# EBS_2020.net
KiCad netlist of a schematic drawn in Altium Designer
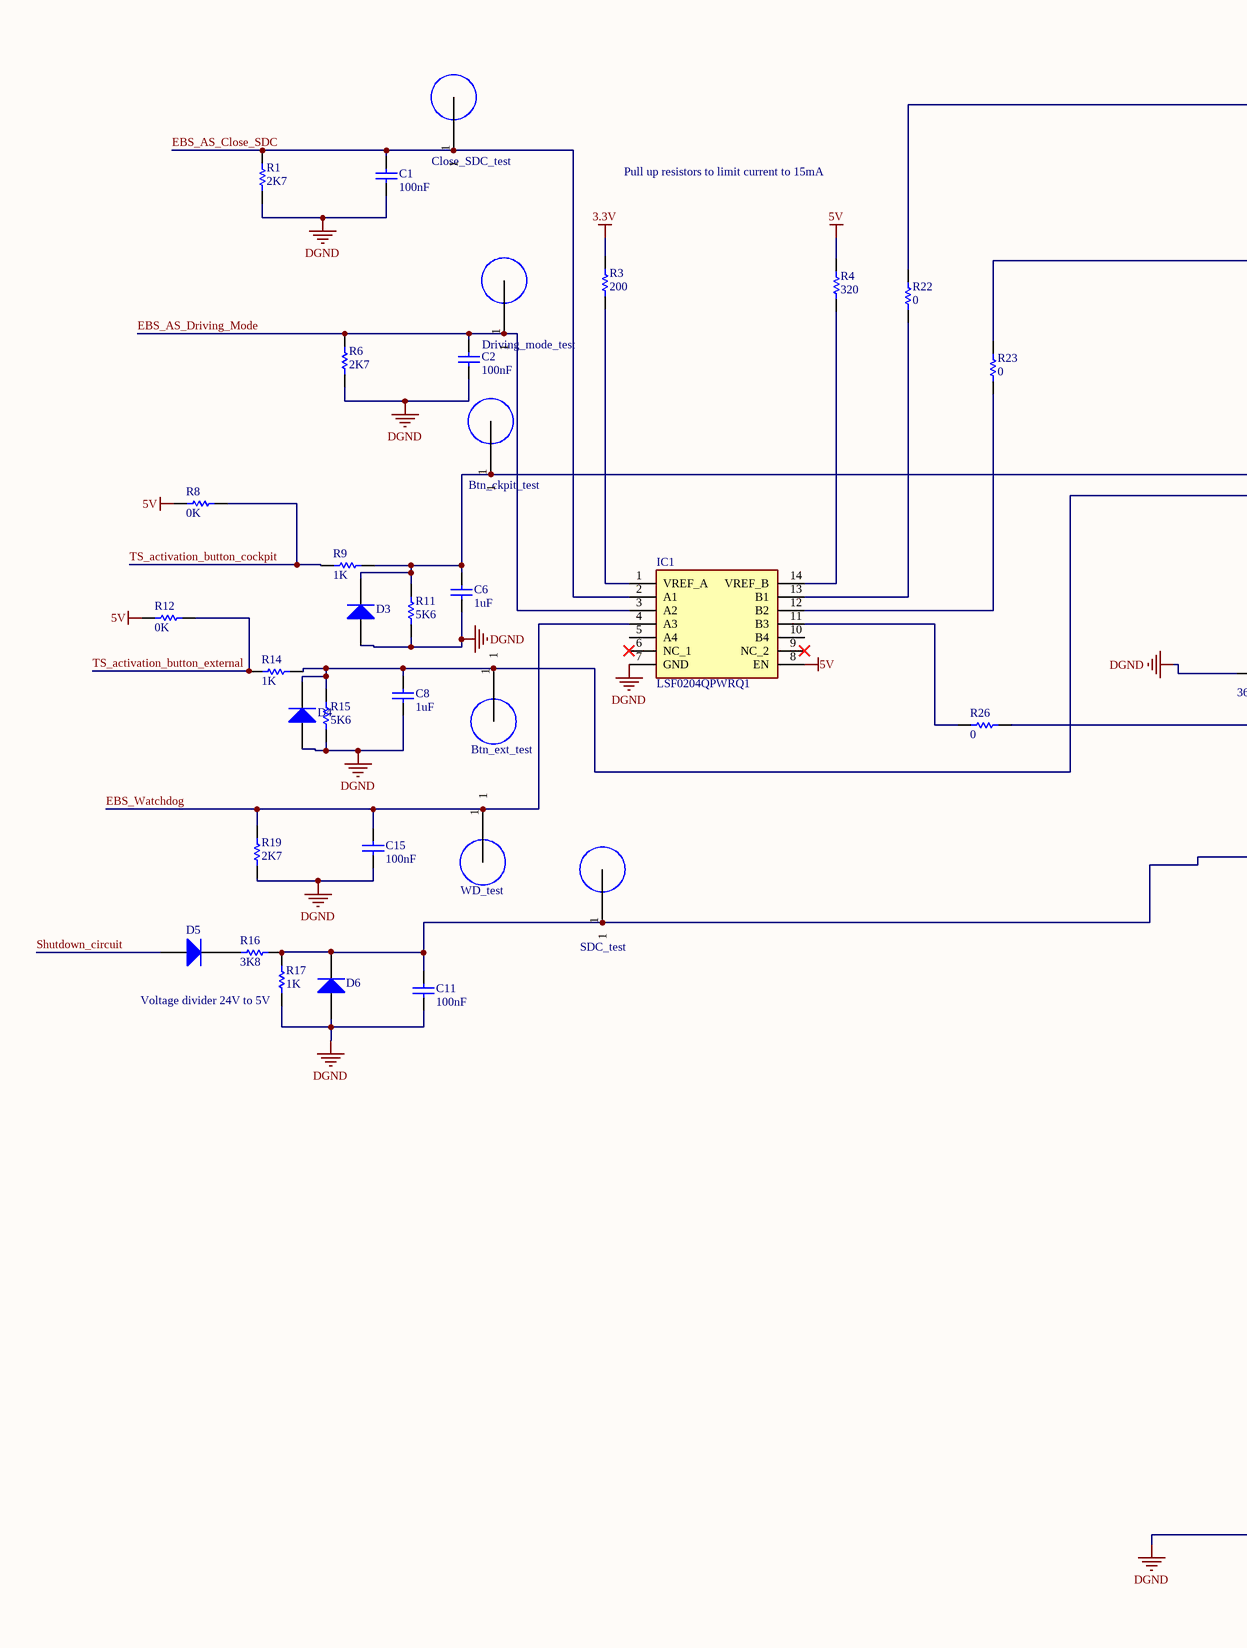
[diagram p0: EBS_2020.SchDoc, left]
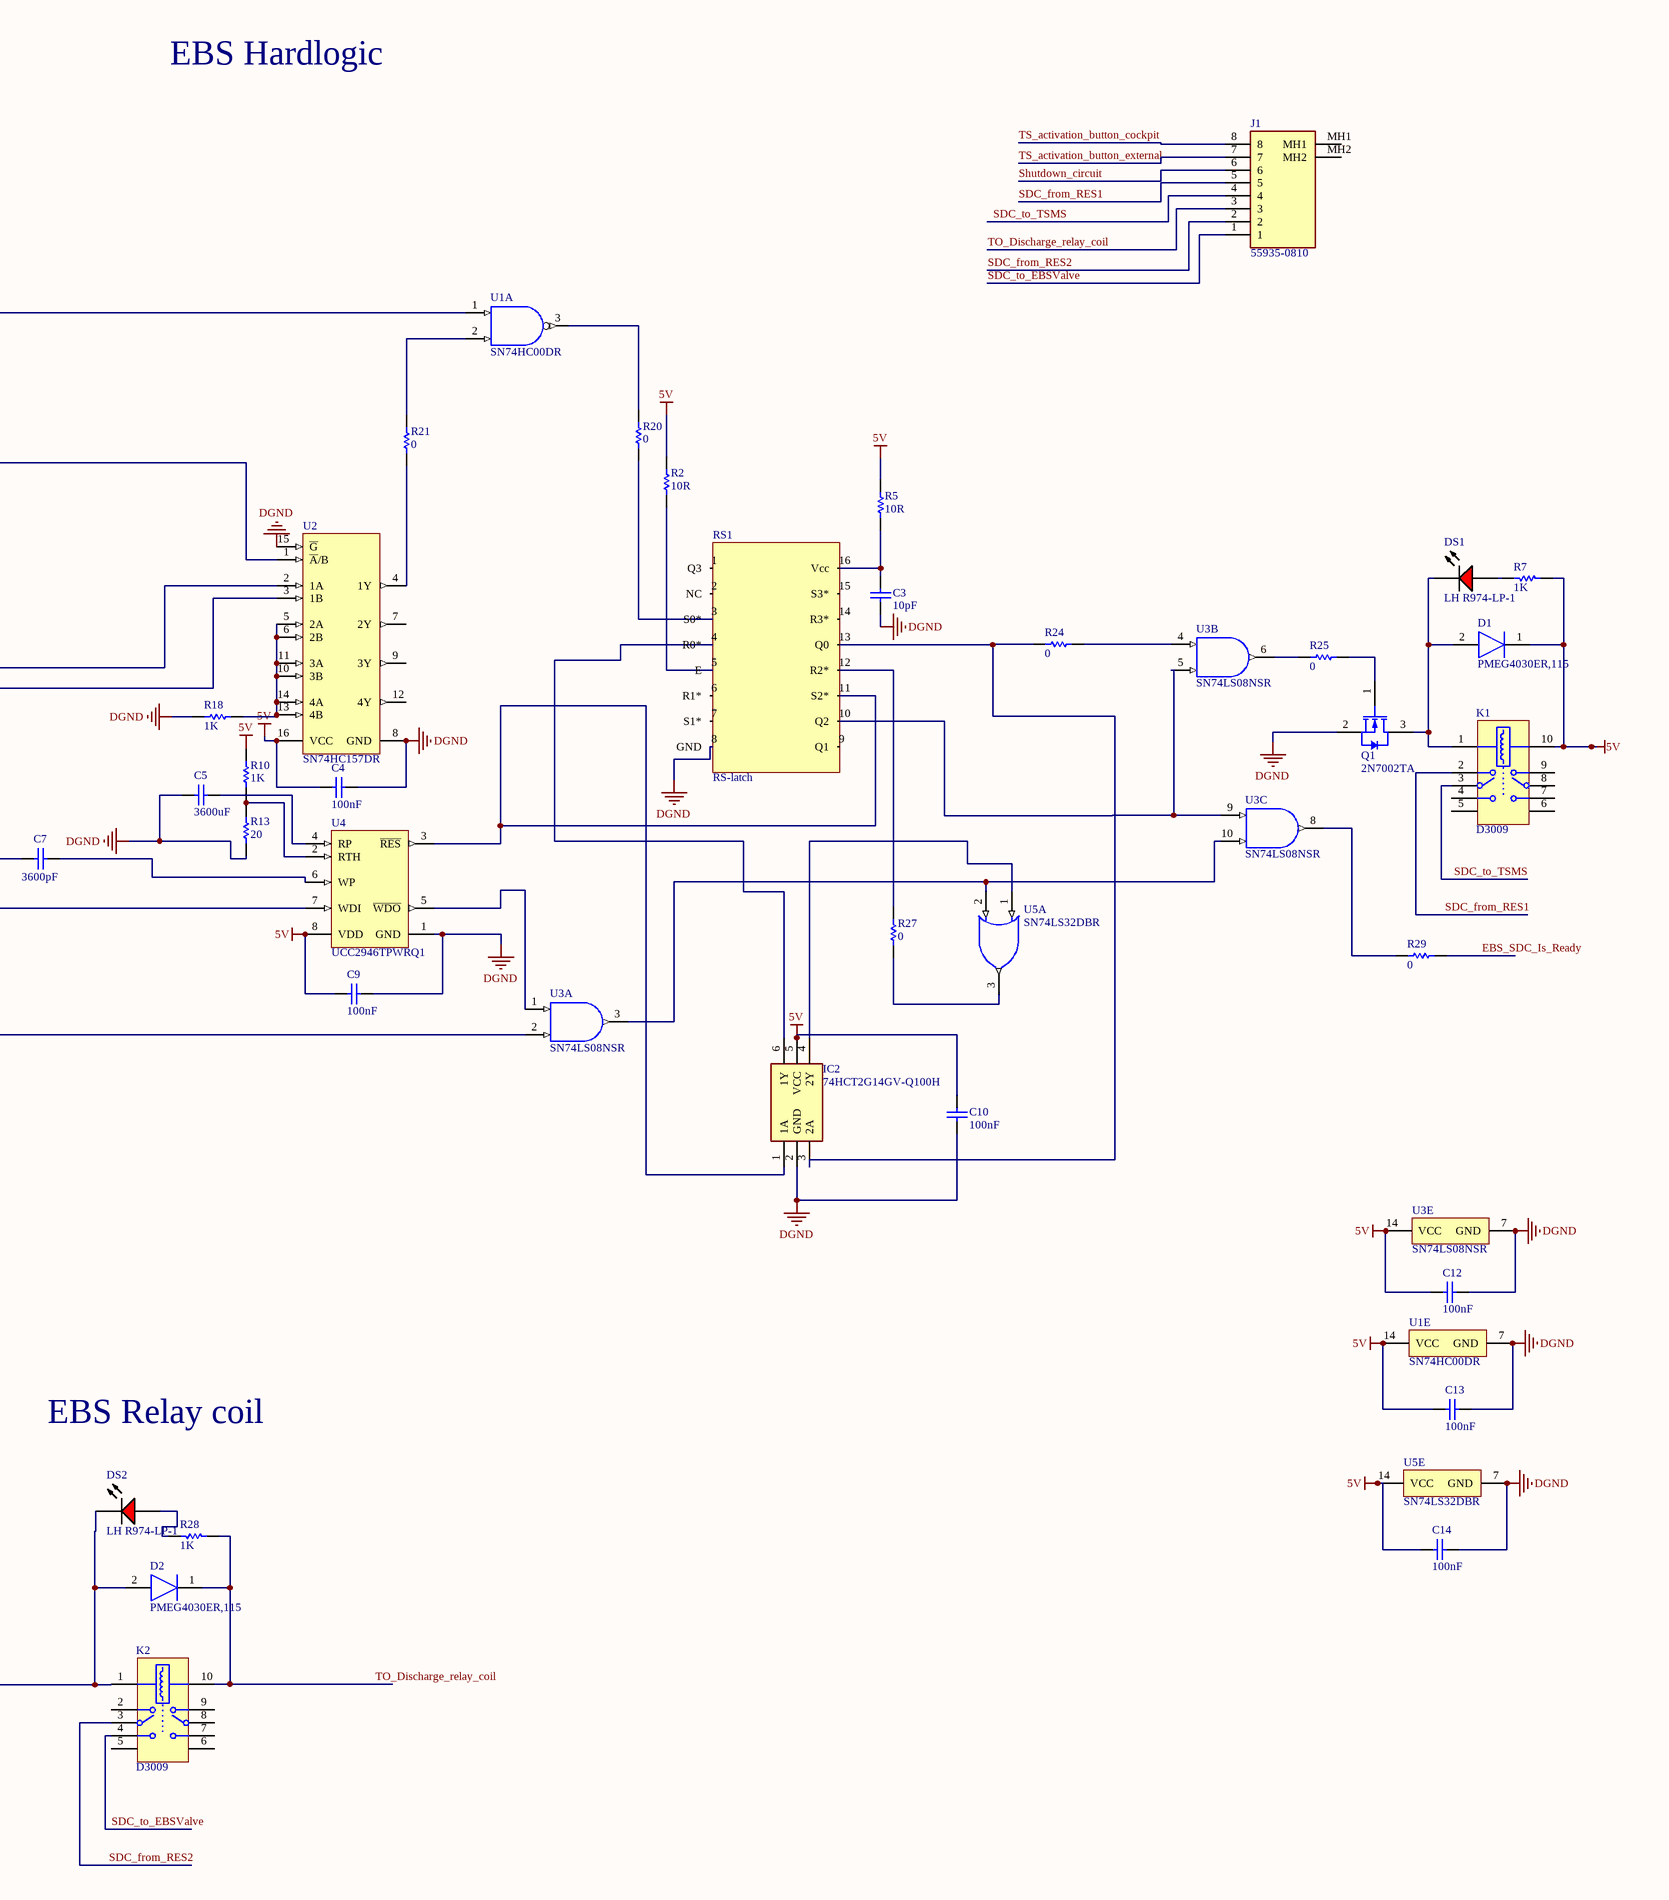
[diagram p1: EBS_2020.SchDoc, right]

(export (version "E")
  (design (tool "Eeschema 10.0.6"))
  (components
    (comp (ref "Btn_ckpit_test")
      (value "MeasuringPoint")
      (footprint "MeasuringPoint")
      (description "1,2mm hole for measuring purpose. Designator should be signal name.")
      (libsource (lib "MeasuringPoint") (part "MeasuringPoint"))
    )
    (comp (ref "Btn_ext_test")
      (value "MeasuringPoint")
      (footprint "MeasuringPoint")
      (description "1,2mm hole for measuring purpose. Designator should be signal name.")
      (libsource (lib "MeasuringPoint") (part "MeasuringPoint"))
    )
    (comp (ref "C1")
      (value "100nF")
      (footprint "dV_C0805")
      (description "CAP 100nF 10V ±20% 0805 (2012 Metric) Thickness 0.75mm SMD")
      (fields (field (name "TOLERANCE") "Â±20%"))
      (libsource (lib "Miscellaneous Devices") (part "CAP"))
    )
    (comp (ref "C2")
      (value "100nF")
      (footprint "dV_C0805")
      (description "CAP 100nF 10V ±20% 0805 (2012 Metric) Thickness 0.75mm SMD")
      (fields (field (name "TOLERANCE") "Â±20%"))
      (libsource (lib "Miscellaneous Devices") (part "CAP"))
    )
    (comp (ref "C3")
      (value "10pF")
      (footprint "CAPC0805(2012)100_N")
      (description "CAP 10pF 16V ±0.5pF 0805 (2012 Metric) Thickness 1mm SMD")
      (fields (field (name "TOLERANCE") "Â±0.5pF"))
      (libsource (lib "Altium Content Vault") (part "CAP"))
    )
    (comp (ref "C4")
      (value "100nF")
      (footprint "dV_C0805")
      (description "CAP 100nF 10V ±20% 0805 (2012 Metric) Thickness 0.75mm SMD")
      (fields (field (name "TOLERANCE") "Â±20%"))
      (libsource (lib "Miscellaneous Devices") (part "CAP"))
    )
    (comp (ref "C5")
      (value "3600uF")
      (footprint "dV_C0805")
      (description "CAP 100nF 10V ±20% 0805 (2012 Metric) Thickness 0.75mm SMD")
      (fields (field (name "TOLERANCE") "Â±20%"))
      (libsource (lib "Miscellaneous Devices") (part "CAP"))
    )
    (comp (ref "C6")
      (value "1uF")
      (footprint "dV_C0805")
      (description "CAP 100nF 10V ±20% 0805 (2012 Metric) Thickness 0.75mm SMD")
      (fields (field (name "TOLERANCE") "Â±20%"))
      (libsource (lib "Miscellaneous Devices") (part "CAP"))
    )
    (comp (ref "C7")
      (value "3600pF")
      (footprint "dV_C0805")
      (fields
        (field (name "MANUFACTURER") "KEMET")
        (field (name "MANUFACTURER PART NUMBER") "C1206C362J5GACTU")
        (field (name "VOLTAGE") "50VDC")
      )
      (libsource (lib "altium-import") (part "root_2_Cap_"))
    )
    (comp (ref "C8")
      (value "1uF")
      (footprint "dV_C0805")
      (description "CAP 100nF 10V ±20% 0805 (2012 Metric) Thickness 0.75mm SMD")
      (fields (field (name "TOLERANCE") "Â±20%"))
      (libsource (lib "Miscellaneous Devices") (part "CAP"))
    )
    (comp (ref "C9")
      (value "100nF")
      (footprint "dV_C0805")
      (description "CAP 100nF 10V ±20% 0805 (2012 Metric) Thickness 0.75mm SMD")
      (fields (field (name "TOLERANCE") "Â±20%"))
      (libsource (lib "Miscellaneous Devices") (part "CAP"))
    )
    (comp (ref "C10")
      (value "100nF")
      (footprint "dV_C0805")
      (description "CAP 100nF 10V ±20% 0805 (2012 Metric) Thickness 0.75mm SMD")
      (fields (field (name "TOLERANCE") "Â±20%"))
      (libsource (lib "Miscellaneous Devices") (part "CAP"))
    )
    (comp (ref "C11")
      (value "100nF")
      (footprint "dV_C0805")
      (description "CAP 100nF 10V ±20% 0805 (2012 Metric) Thickness 0.75mm SMD")
      (fields (field (name "TOLERANCE") "Â±20%"))
      (libsource (lib "Miscellaneous Devices") (part "CAP"))
    )
    (comp (ref "C12")
      (value "100nF")
      (footprint "dV_C0805")
      (description "CAP 100nF 10V ±20% 0805 (2012 Metric) Thickness 0.75mm SMD")
      (fields (field (name "TOLERANCE") "Â±20%"))
      (libsource (lib "Miscellaneous Devices") (part "CAP"))
    )
    (comp (ref "C13")
      (value "100nF")
      (footprint "dV_C0805")
      (description "CAP 100nF 10V ±20% 0805 (2012 Metric) Thickness 0.75mm SMD")
      (fields (field (name "TOLERANCE") "Â±20%"))
      (libsource (lib "Miscellaneous Devices") (part "CAP"))
    )
    (comp (ref "C14")
      (value "100nF")
      (footprint "dV_C0805")
      (description "CAP 100nF 10V ±20% 0805 (2012 Metric) Thickness 0.75mm SMD")
      (fields (field (name "TOLERANCE") "Â±20%"))
      (libsource (lib "Miscellaneous Devices") (part "CAP"))
    )
    (comp (ref "C15")
      (value "100nF")
      (footprint "dV_C0805")
      (description "CAP 100nF 10V ±20% 0805 (2012 Metric) Thickness 0.75mm SMD")
      (fields (field (name "TOLERANCE") "Â±20%"))
      (libsource (lib "Miscellaneous Devices") (part "CAP"))
    )
    (comp (ref "Close_SDC_test")
      (value "MeasuringPoint")
      (footprint "MeasuringPoint")
      (description "1,2mm hole for measuring purpose. Designator should be signal name.")
      (libsource (lib "MeasuringPoint") (part "MeasuringPoint"))
    )
    (comp (ref "D1")
      (value "PMEG4030ER,115")
      (footprint "SamacSys:SODFL3517X110N")
      (description "Diode")
      (fields (field (name "MOUSER2 PART NUMBER") "771-PMEG4030ER115"))
      (libsource (lib "*") (part "PMEG4030ER,115"))
    )
    (comp (ref "D2")
      (value "PMEG4030ER,115")
      (footprint "SamacSys:SODFL3517X110N")
      (description "Diode")
      (fields (field (name "MOUSER2 PART NUMBER") "771-PMEG4030ER115"))
      (libsource (lib "*") (part "PMEG4030ER,115"))
    )
    (comp (ref "D3")
      (value "~")
      (footprint "1SMA12AT3G")
      (description "High Conductance Fast Diode")
      (fields
        (field (name "MANUFACTURER") "PANASONIC ELECTRONIC COMPONENTS")
        (field (name "MANUFACTURER PART NUMBER") "DB2W31900L")
      )
      (libsource (lib "Miscellaneous Devices") (part "Diode 1N914"))
    )
    (comp (ref "D4")
      (value "~")
      (footprint "1SMA12AT3G")
      (description "High Conductance Fast Diode")
      (fields
        (field (name "MANUFACTURER") "PANASONIC ELECTRONIC COMPONENTS")
        (field (name "MANUFACTURER PART NUMBER") "DB2W31900L")
      )
      (libsource (lib "Miscellaneous Devices") (part "Diode 1N914"))
    )
    (comp (ref "D5")
      (value "~")
      (footprint "1SMA12AT3G")
      (description "High Conductance Fast Diode")
      (fields
        (field (name "MANUFACTURER") "PANASONIC ELECTRONIC COMPONENTS")
        (field (name "MANUFACTURER PART NUMBER") "DB2W31900L")
      )
      (libsource (lib "Miscellaneous Devices") (part "Diode 1N914"))
    )
    (comp (ref "D6")
      (value "~")
      (footprint "1SMA12AT3G")
      (description "High Conductance Fast Diode")
      (fields
        (field (name "MANUFACTURER") "PANASONIC ELECTRONIC COMPONENTS")
        (field (name "MANUFACTURER PART NUMBER") "DB2W31900L")
      )
      (libsource (lib "Miscellaneous Devices") (part "Diode 1N914"))
    )
    (comp (ref "Driving_mode_test")
      (value "MeasuringPoint")
      (footprint "MeasuringPoint")
      (description "1,2mm hole for measuring purpose. Designator should be signal name.")
      (libsource (lib "MeasuringPoint") (part "MeasuringPoint"))
    )
    (comp (ref "DS1")
      (value "LH R974-LP-1")
      (footprint "OSRM-LH R974_V")
      (description "LED Uni-Color Red, 1.8 V, -30 to 85 degC, 2-Pin SMD, RoHS, Tape and Reel")
      (fields (field (name "MANUFACTURER") "OSRAM"))
      (libsource (lib "Altium Content Vault") (part "LED-RED-AK-2"))
    )
    (comp (ref "DS2")
      (value "LH R974-LP-1")
      (footprint "OSRM-LH R974_V")
      (description "LED Uni-Color Red, 1.8 V, -30 to 85 degC, 2-Pin SMD, RoHS, Tape and Reel")
      (fields (field (name "MANUFACTURER") "OSRAM"))
      (libsource (lib "Altium Content Vault") (part "LED-RED-AK-2"))
    )
    (comp (ref "IC1")
      (value "LSF0204QPWRQ1")
      (footprint "SamacSys:SOP65P640X120-14N")
      (description "Integrated Circuit")
      (fields (field (name "MOUSER2 PART NUMBER") "595-LSF0204QPWRQ1"))
      (libsource (lib "*") (part "LSF0204QPWRQ1"))
    )
    (comp (ref "IC2")
      (value "74HCT2G14GV-Q100H")
      (footprint "SamacSys:SOT95P275X110-6N")
      (description "Integrated Circuit")
      (libsource (lib "*") (part "74HCT2G14GV-Q100H"))
    )
    (comp (ref "J1")
      (value "55935-0810")
      (footprint "SamacSys:559350810")
      (description "Connector")
      (libsource (lib "*") (part "55935-0810"))
    )
    (comp (ref "K1")
      (value "D3009")
      (footprint "TECO-FP2-10_V")
      (description "2 Form C, Monostable FP2 Relay, 2 A, 5 V, 10-Pin THT(FP2), RoHS, Tube")
      (fields (field (name "MANUFACTURER") "TE Connectivity"))
      (libsource (lib "Altium Content Vault") (part "TECO-D300_301_302_304"))
    )
    (comp (ref "K2")
      (value "D3009")
      (footprint "TECO-FP2-10_V")
      (description "2 Form C, Monostable FP2 Relay, 2 A, 5 V, 10-Pin THT(FP2), RoHS, Tube")
      (fields (field (name "MANUFACTURER") "TE Connectivity"))
      (libsource (lib "Altium Content Vault") (part "TECO-D300_301_302_304"))
    )
    (comp (ref "Q1")
      (value "2N7002TA")
      (footprint "DIOD-SOT23-3_V")
      (fields (field (name "MANUFACTURER") "DiodesIncorporated"))
      (libsource (lib "Altium Content Vault") (part "NEMOS-GSD-3"))
    )
    (comp (ref "R1")
      (value "2K7")
      (footprint "dV_R0805")
      (description "2K7 0.125W 1% 0805 (2012 Metric)  SMD")
      (fields (field (name "TOLERANCE") "1 %") (field (name "POWER") "0.125 W"))
      (libsource (lib "BSPDLib") (part "RES"))
    )
    (comp (ref "R2")
      (value "10R")
      (footprint "RESC0805(2012)_N")
      (description "10R 0.125W 1% 0805 (2012 Metric)  SMD")
      (fields (field (name "TOLERANCE") "1 %") (field (name "POWER") "0.125 W"))
      (libsource (lib "Altium Content Vault") (part "RES"))
    )
    (comp (ref "R3")
      (value "200")
      (footprint "dV_R0805")
      (description "2K7 0.125W 1% 0805 (2012 Metric)  SMD")
      (fields (field (name "TOLERANCE") "1 %") (field (name "POWER") "0.125 W"))
      (libsource (lib "BSPDLib") (part "RES"))
    )
    (comp (ref "R4")
      (value "320")
      (footprint "dV_R0805")
      (description "2K7 0.125W 1% 0805 (2012 Metric)  SMD")
      (fields (field (name "TOLERANCE") "1 %") (field (name "POWER") "0.125 W"))
      (libsource (lib "BSPDLib") (part "RES"))
    )
    (comp (ref "R5")
      (value "10R")
      (footprint "RESC0805(2012)_N")
      (description "10R 0.125W 1% 0805 (2012 Metric)  SMD")
      (fields (field (name "TOLERANCE") "1 %") (field (name "POWER") "0.125 W"))
      (libsource (lib "Altium Content Vault") (part "RES"))
    )
    (comp (ref "R6")
      (value "2K7")
      (footprint "dV_R0805")
      (description "2K7 0.125W 1% 0805 (2012 Metric)  SMD")
      (fields (field (name "TOLERANCE") "1 %") (field (name "POWER") "0.125 W"))
      (libsource (lib "BSPDLib") (part "RES"))
    )
    (comp (ref "R7")
      (value "1K")
      (footprint "dV_R0805")
      (description "1K 0.125W 1% 0805 (2012 Metric)  SMD")
      (fields (field (name "TOLERANCE") "1 %") (field (name "POWER") "0.125 W"))
      (libsource (lib "Miscellaneous Devices") (part "RES"))
    )
    (comp (ref "R8")
      (value "0K")
      (footprint "dV_R0805")
      (description "2K7 0.125W 1% 0805 (2012 Metric)  SMD")
      (fields (field (name "TOLERANCE") "1 %") (field (name "POWER") "0.125 W"))
      (libsource (lib "BSPDLib") (part "RES"))
    )
    (comp (ref "R9")
      (value "1K")
      (footprint "dV_R0805")
      (description "2K7 0.125W 1% 0805 (2012 Metric)  SMD")
      (fields (field (name "TOLERANCE") "1 %") (field (name "POWER") "0.125 W"))
      (libsource (lib "BSPDLib") (part "RES"))
    )
    (comp (ref "R10")
      (value "1K")
      (footprint "dV_R0805")
      (description "2K7 0.125W 1% 0805 (2012 Metric)  SMD")
      (fields (field (name "TOLERANCE") "1 %") (field (name "POWER") "0.125 W"))
      (libsource (lib "BSPDLib") (part "RES"))
    )
    (comp (ref "R11")
      (value "5K6")
      (footprint "dV_R0805")
      (description "2K7 0.125W 1% 0805 (2012 Metric)  SMD")
      (fields (field (name "TOLERANCE") "1 %") (field (name "POWER") "0.125 W"))
      (libsource (lib "BSPDLib") (part "RES"))
    )
    (comp (ref "R12")
      (value "0K")
      (footprint "dV_R0805")
      (description "2K7 0.125W 1% 0805 (2012 Metric)  SMD")
      (fields (field (name "TOLERANCE") "1 %") (field (name "POWER") "0.125 W"))
      (libsource (lib "BSPDLib") (part "RES"))
    )
    (comp (ref "R13")
      (value "20")
      (footprint "dV_R0805")
      (description "2K7 0.125W 1% 0805 (2012 Metric)  SMD")
      (fields (field (name "TOLERANCE") "1 %") (field (name "POWER") "0.125 W"))
      (libsource (lib "BSPDLib") (part "RES"))
    )
    (comp (ref "R14")
      (value "1K")
      (footprint "dV_R0805")
      (description "2K7 0.125W 1% 0805 (2012 Metric)  SMD")
      (fields (field (name "TOLERANCE") "1 %") (field (name "POWER") "0.125 W"))
      (libsource (lib "BSPDLib") (part "RES"))
    )
    (comp (ref "R15")
      (value "5K6")
      (footprint "dV_R0805")
      (description "2K7 0.125W 1% 0805 (2012 Metric)  SMD")
      (fields (field (name "TOLERANCE") "1 %") (field (name "POWER") "0.125 W"))
      (libsource (lib "BSPDLib") (part "RES"))
    )
    (comp (ref "R16")
      (value "3K8")
      (footprint "dV_R0805")
      (description "2K7 0.125W 1% 0805 (2012 Metric)  SMD")
      (fields (field (name "TOLERANCE") "1 %") (field (name "POWER") "0.125 W"))
      (libsource (lib "BSPDLib") (part "RES"))
    )
    (comp (ref "R17")
      (value "1K")
      (footprint "dV_R0805")
      (description "2K7 0.125W 1% 0805 (2012 Metric)  SMD")
      (fields (field (name "TOLERANCE") "1 %") (field (name "POWER") "0.125 W"))
      (libsource (lib "BSPDLib") (part "RES"))
    )
    (comp (ref "R18")
      (value "1K")
      (footprint "dV_R0805")
      (description "2K7 0.125W 1% 0805 (2012 Metric)  SMD")
      (fields (field (name "TOLERANCE") "1 %") (field (name "POWER") "0.125 W"))
      (libsource (lib "BSPDLib") (part "RES"))
    )
    (comp (ref "R19")
      (value "2K7")
      (footprint "dV_R0805")
      (description "2K7 0.125W 1% 0805 (2012 Metric)  SMD")
      (fields (field (name "TOLERANCE") "1 %") (field (name "POWER") "0.125 W"))
      (libsource (lib "BSPDLib") (part "RES"))
    )
    (comp (ref "R20")
      (value "0")
      (footprint "dV_R0805")
      (description "2K7 0.125W 1% 0805 (2012 Metric)  SMD")
      (fields (field (name "TOLERANCE") "1 %") (field (name "POWER") "0.125 W"))
      (libsource (lib "BSPDLib") (part "RES"))
    )
    (comp (ref "R21")
      (value "0")
      (footprint "dV_R0805")
      (description "2K7 0.125W 1% 0805 (2012 Metric)  SMD")
      (fields (field (name "TOLERANCE") "1 %") (field (name "POWER") "0.125 W"))
      (libsource (lib "BSPDLib") (part "RES"))
    )
    (comp (ref "R22")
      (value "0")
      (footprint "dV_R0805")
      (description "2K7 0.125W 1% 0805 (2012 Metric)  SMD")
      (fields (field (name "TOLERANCE") "1 %") (field (name "POWER") "0.125 W"))
      (libsource (lib "BSPDLib") (part "RES"))
    )
    (comp (ref "R23")
      (value "0")
      (footprint "dV_R0805")
      (description "2K7 0.125W 1% 0805 (2012 Metric)  SMD")
      (fields (field (name "TOLERANCE") "1 %") (field (name "POWER") "0.125 W"))
      (libsource (lib "BSPDLib") (part "RES"))
    )
    (comp (ref "R24")
      (value "0")
      (footprint "dV_R0805")
      (description "2K7 0.125W 1% 0805 (2012 Metric)  SMD")
      (fields (field (name "TOLERANCE") "1 %") (field (name "POWER") "0.125 W"))
      (libsource (lib "BSPDLib") (part "RES"))
    )
    (comp (ref "R25")
      (value "0")
      (footprint "dV_R0805")
      (description "2K7 0.125W 1% 0805 (2012 Metric)  SMD")
      (fields (field (name "TOLERANCE") "1 %") (field (name "POWER") "0.125 W"))
      (libsource (lib "BSPDLib") (part "RES"))
    )
    (comp (ref "R26")
      (value "0")
      (footprint "dV_R0805")
      (description "2K7 0.125W 1% 0805 (2012 Metric)  SMD")
      (fields (field (name "TOLERANCE") "1 %") (field (name "POWER") "0.125 W"))
      (libsource (lib "BSPDLib") (part "RES"))
    )
    (comp (ref "R27")
      (value "0")
      (footprint "dV_R0805")
      (description "2K7 0.125W 1% 0805 (2012 Metric)  SMD")
      (fields (field (name "TOLERANCE") "1 %") (field (name "POWER") "0.125 W"))
      (libsource (lib "BSPDLib") (part "RES"))
    )
    (comp (ref "R28")
      (value "1K")
      (footprint "dV_R0805")
      (description "1K 0.125W 1% 0805 (2012 Metric)  SMD")
      (fields (field (name "TOLERANCE") "1 %") (field (name "POWER") "0.125 W"))
      (libsource (lib "Miscellaneous Devices") (part "RES"))
    )
    (comp (ref "R29")
      (value "0")
      (footprint "dV_R0805")
      (description "2K7 0.125W 1% 0805 (2012 Metric)  SMD")
      (fields (field (name "TOLERANCE") "1 %") (field (name "POWER") "0.125 W"))
      (libsource (lib "BSPDLib") (part "RES"))
    )
    (comp (ref "RS1")
      (value "RS-latch")
      (footprint "SOIC127P600X175-16N")
      (description "MC14044B")
      (libsource (lib "BSPDLib") (part "RS-latch"))
    )
    (comp (ref "SDC_test")
      (value "MeasuringPoint")
      (footprint "MeasuringPoint")
      (description "1,2mm hole for measuring purpose. Designator should be signal name.")
      (libsource (lib "MeasuringPoint") (part "MeasuringPoint"))
    )
    (comp (ref "U1")
      (value "SN74HC00DR")
      (footprint "D0014A_M")
      (description "Quad 2-Input Positive-NAND Gates, D0014A, LARGE T&R")
      (fields
        (field (name "GENERIC PART NUMBER") "SN74HC00")
        (field (name "MANUFACTURER") "Texas Instruments")
      )
      (libsource (lib "Altium Content Vault") (part "TI-NAND-4-2IN-14_G"))
    )
    (comp (ref "U2")
      (value "SN74HC157DR")
      (footprint "D0016A_M")
      (description "Quadruple 2-Line To 1-Line Data Selectors/Multiplexers, D0016A, LARGE T&R")
      (fields
        (field (name "MANUFACTURER") "Texas Instruments")
        (field (name "GENERIC PART NUMBER") "SN74HC157")
      )
      (libsource (lib "Altium Content Vault") (part "TI-XXX4XXXX15XX-16"))
    )
    (comp (ref "U3")
      (value "SN74LS08NSR")
      (footprint "NS0014A_L")
      (description "Quadruple 2-Input Positive-AND Gates, NS0014A, LARGE T&R")
      (fields
        (field (name "MANUFACTURER") "Texas Instruments")
        (field (name "GENERIC PART NUMBER") "SN74LS08")
      )
      (libsource (lib "Altium Content Vault") (part "TI-AND-4-2IN-14"))
    )
    (comp (ref "U4")
      (value "UCC2946TPWRQ1")
      (footprint "PW8_N")
      (fields (field (name "MANUFACTURER") "Texas Instruments"))
      (libsource (lib "TI Power Management Supervisor and Reset IC") (part "UCC2946TPWRQ1"))
    )
    (comp (ref "U5")
      (value "SN74LS32DBR")
      (footprint "DB0014A_N")
      (description "Quad 2-input positive-OR gates, DB0014A, LARGE T&R")
      (fields
        (field (name "GENERIC PART NUMBER") "SN74LS32")
        (field (name "MANUFACTURER") "Texas Instruments")
      )
      (libsource (lib "Altium Content Vault") (part "TI-OR-4-2IN-14"))
    )
    (comp (ref "WD_test")
      (value "MeasuringPoint")
      (footprint "MeasuringPoint")
      (description "1,2mm hole for measuring purpose. Designator should be signal name.")
      (libsource (lib "MeasuringPoint") (part "MeasuringPoint"))
    )
  )
  (nets
    (net (code "1") (name "/EBS_AS_Close_SDC") (class "Default")
      (node (ref "C1") (pin "2") (pinfunction "2_2") (pintype "passive"))
      (node (ref "Close_SDC_test") (pin "1") (pinfunction "1_1") (pintype "passive"))
      (node (ref "IC1") (pin "2") (pinfunction "A1_2") (pintype "passive"))
      (node (ref "R1") (pin "2") (pinfunction "2_2") (pintype "passive"))
    )
    (net (code "2") (name "/EBS_AS_Driving_Mode") (class "Default")
      (node (ref "C2") (pin "2") (pinfunction "2_2") (pintype "passive"))
      (node (ref "Driving_mode_test") (pin "1") (pinfunction "1_1") (pintype "passive"))
      (node (ref "IC1") (pin "3") (pinfunction "A2_3") (pintype "passive"))
      (node (ref "R6") (pin "2") (pinfunction "2_2") (pintype "passive"))
    )
    (net (code "3") (name "/EBS_SDC_Is_Ready") (class "Default")
      (node (ref "R29") (pin "2") (pinfunction "2_2") (pintype "passive"))
    )
    (net (code "4") (name "/EBS_Watchdog") (class "Default")
      (node (ref "C15") (pin "2") (pinfunction "2_2") (pintype "passive"))
      (node (ref "IC1") (pin "4") (pinfunction "A3_4") (pintype "passive"))
      (node (ref "R19") (pin "2") (pinfunction "2_2") (pintype "passive"))
      (node (ref "WD_test") (pin "1") (pinfunction "1_1") (pintype "passive"))
    )
    (net (code "5") (name "/SDC_from_RES1") (class "Default")
      (node (ref "J1") (pin "5") (pinfunction "5_5") (pintype "passive"))
      (node (ref "K1") (pin "2") (pinfunction "2_2") (pintype "passive"))
    )
    (net (code "6") (name "/SDC_from_RES2") (class "Default")
      (node (ref "J1") (pin "2") (pinfunction "2_2") (pintype "passive"))
      (node (ref "K2") (pin "3") (pinfunction "3_3") (pintype "passive"))
    )
    (net (code "7") (name "/SDC_to_EBSValve") (class "Default")
      (node (ref "J1") (pin "1") (pinfunction "1_1") (pintype "passive"))
      (node (ref "K2") (pin "4") (pinfunction "4_4") (pintype "passive"))
    )
    (net (code "8") (name "/SDC_to_TSMS") (class "Default")
      (node (ref "J1") (pin "4") (pinfunction "4_4") (pintype "passive"))
      (node (ref "K1") (pin "3") (pinfunction "3_3") (pintype "passive"))
    )
    (net (code "9") (name "/Shutdown_circuit") (class "Default")
      (node (ref "D5") (pin "1") (pinfunction "A_1") (pintype "passive"))
      (node (ref "J1") (pin "6") (pinfunction "6_6") (pintype "passive"))
    )
    (net (code "10") (name "/TO_Discharge_relay_coil") (class "Default")
      (node (ref "D2") (pin "1") (pinfunction "K_1") (pintype "passive"))
      (node (ref "J1") (pin "3") (pinfunction "3_3") (pintype "passive"))
      (node (ref "K2") (pin "10") (pinfunction "10_10") (pintype "passive"))
      (node (ref "R28") (pin "1") (pinfunction "1_1") (pintype "passive"))
    )
    (net (code "11") (name "/TS_activation_button_cockpit") (class "Default")
      (node (ref "J1") (pin "8") (pinfunction "8_8") (pintype "passive"))
      (node (ref "R8") (pin "1") (pinfunction "1_1") (pintype "passive"))
      (node (ref "R9") (pin "2") (pinfunction "2_2") (pintype "passive"))
    )
    (net (code "12") (name "/TS_activation_button_external") (class "Default")
      (node (ref "J1") (pin "7") (pinfunction "7_7") (pintype "passive"))
      (node (ref "R12") (pin "1") (pinfunction "1_1") (pintype "passive"))
      (node (ref "R14") (pin "2") (pinfunction "2_2") (pintype "passive"))
    )
    (net (code "13") (name "3.3V") (class "Default")
      (node (ref "R3") (pin "1") (pinfunction "1_1") (pintype "passive"))
    )
    (net (code "14") (name "5V") (class "Default")
      (node (ref "C10") (pin "1") (pinfunction "1_1") (pintype "passive"))
      (node (ref "C12") (pin "2") (pinfunction "2_2") (pintype "passive"))
      (node (ref "C13") (pin "2") (pinfunction "2_2") (pintype "passive"))
      (node (ref "C14") (pin "2") (pinfunction "2_2") (pintype "passive"))
      (node (ref "C4") (pin "2") (pinfunction "2_2") (pintype "passive"))
      (node (ref "C9") (pin "2") (pinfunction "2_2") (pintype "passive"))
      (node (ref "D1") (pin "1") (pinfunction "K_1") (pintype "passive"))
      (node (ref "IC1") (pin "8") (pinfunction "EN_8") (pintype "passive"))
      (node (ref "IC2") (pin "5") (pinfunction "VCC_5") (pintype "passive"))
      (node (ref "K1") (pin "10") (pinfunction "10_10") (pintype "passive"))
      (node (ref "R10") (pin "2") (pinfunction "2_2") (pintype "passive"))
      (node (ref "R12") (pin "2") (pinfunction "2_2") (pintype "passive"))
      (node (ref "R2") (pin "2") (pinfunction "2_2") (pintype "passive"))
      (node (ref "R4") (pin "1") (pinfunction "1_1") (pintype "passive"))
      (node (ref "R5") (pin "2") (pinfunction "2_2") (pintype "passive"))
      (node (ref "R7") (pin "1") (pinfunction "1_1") (pintype "passive"))
      (node (ref "R8") (pin "2") (pinfunction "2_2") (pintype "passive"))
      (node (ref "U1") (pin "14") (pinfunction "VCC_14") (pintype "power_in"))
      (node (ref "U2") (pin "16") (pinfunction "VCC_16") (pintype "power_in"))
      (node (ref "U3") (pin "14") (pinfunction "VCC_14") (pintype "power_in"))
      (node (ref "U4") (pin "8") (pinfunction "VDD_8") (pintype "power_in"))
      (node (ref "U5") (pin "14") (pinfunction "VCC_14") (pintype "power_in"))
    )
    (net (code "15") (name "DGND") (class "Default")
      (node (ref "C1") (pin "1") (pinfunction "1_1") (pintype "passive"))
      (node (ref "C10") (pin "2") (pinfunction "2_2") (pintype "passive"))
      (node (ref "C11") (pin "1") (pinfunction "1_1") (pintype "passive"))
      (node (ref "C12") (pin "1") (pinfunction "1_1") (pintype "passive"))
      (node (ref "C13") (pin "1") (pinfunction "1_1") (pintype "passive"))
      (node (ref "C14") (pin "1") (pinfunction "1_1") (pintype "passive"))
      (node (ref "C15") (pin "1") (pinfunction "1_1") (pintype "passive"))
      (node (ref "C2") (pin "1") (pinfunction "1_1") (pintype "passive"))
      (node (ref "C3") (pin "1") (pinfunction "1_1") (pintype "passive"))
      (node (ref "C4") (pin "1") (pinfunction "1_1") (pintype "passive"))
      (node (ref "C5") (pin "2") (pinfunction "2_2") (pintype "passive"))
      (node (ref "C6") (pin "1") (pinfunction "1_1") (pintype "passive"))
      (node (ref "C7") (pin "2") (pinfunction "2_2") (pintype "passive"))
      (node (ref "C8") (pin "1") (pinfunction "1_1") (pintype "passive"))
      (node (ref "C9") (pin "1") (pinfunction "1_1") (pintype "passive"))
      (node (ref "D2") (pin "2") (pinfunction "A_2") (pintype "passive"))
      (node (ref "D3") (pin "1") (pinfunction "A_1") (pintype "passive"))
      (node (ref "D4") (pin "1") (pinfunction "A_1") (pintype "passive"))
      (node (ref "D6") (pin "1") (pinfunction "A_1") (pintype "passive"))
      (node (ref "DS2") (pin "2") (pinfunction "K_2") (pintype "passive"))
      (node (ref "IC1") (pin "7") (pinfunction "GND_7") (pintype "passive"))
      (node (ref "IC2") (pin "2") (pinfunction "GND_2") (pintype "passive"))
      (node (ref "K2") (pin "1") (pinfunction "1_1") (pintype "passive"))
      (node (ref "Q1") (pin "2") (pinfunction "S_2") (pintype "passive"))
      (node (ref "R1") (pin "1") (pinfunction "1_1") (pintype "passive"))
      (node (ref "R11") (pin "2") (pinfunction "2_2") (pintype "passive"))
      (node (ref "R13") (pin "1") (pinfunction "1_1") (pintype "passive"))
      (node (ref "R15") (pin "2") (pinfunction "2_2") (pintype "passive"))
      (node (ref "R17") (pin "1") (pinfunction "1_1") (pintype "passive"))
      (node (ref "R18") (pin "2") (pinfunction "2_2") (pintype "passive"))
      (node (ref "R19") (pin "1") (pinfunction "1_1") (pintype "passive"))
      (node (ref "R6") (pin "1") (pinfunction "1_1") (pintype "passive"))
      (node (ref "RS1") (pin "8") (pinfunction "GND_8") (pintype "passive"))
      (node (ref "U1") (pin "7") (pinfunction "GND_7") (pintype "power_in"))
      (node (ref "U2") (pin "15") (pinfunction "~{G}_15") (pintype "input"))
      (node (ref "U2") (pin "8") (pinfunction "GND_8") (pintype "power_in"))
      (node (ref "U3") (pin "7") (pinfunction "GND_7") (pintype "power_in"))
      (node (ref "U4") (pin "1") (pinfunction "GND_1") (pintype "power_in"))
      (node (ref "U5") (pin "7") (pinfunction "GND_7") (pintype "power_in"))
    )
    (net (code "16") (name "Net-(D1-A)") (class "Default")
      (node (ref "D1") (pin "2") (pinfunction "A_2") (pintype "passive"))
      (node (ref "DS1") (pin "2") (pinfunction "K_2") (pintype "passive"))
      (node (ref "K1") (pin "1") (pinfunction "1_1") (pintype "passive"))
      (node (ref "Q1") (pin "3") (pinfunction "D_3") (pintype "passive"))
    )
    (net (code "17") (name "Net-(D3-K)") (class "Default")
      (node (ref "Btn_ckpit_test") (pin "1") (pinfunction "1_1") (pintype "passive"))
      (node (ref "C6") (pin "2") (pinfunction "2_2") (pintype "passive"))
      (node (ref "D3") (pin "2") (pinfunction "K_2") (pintype "passive"))
      (node (ref "R11") (pin "1") (pinfunction "1_1") (pintype "passive"))
      (node (ref "R9") (pin "1") (pinfunction "1_1") (pintype "passive"))
      (node (ref "U2") (pin "2") (pinfunction "1A_2") (pintype "input"))
    )
    (net (code "18") (name "Net-(D4-K)") (class "Default")
      (node (ref "Btn_ext_test") (pin "1") (pinfunction "1_1") (pintype "passive"))
      (node (ref "C8") (pin "2") (pinfunction "2_2") (pintype "passive"))
      (node (ref "D4") (pin "2") (pinfunction "K_2") (pintype "passive"))
      (node (ref "R14") (pin "1") (pinfunction "1_1") (pintype "passive"))
      (node (ref "R15") (pin "1") (pinfunction "1_1") (pintype "passive"))
      (node (ref "U2") (pin "3") (pinfunction "1B_3") (pintype "input"))
    )
    (net (code "19") (name "Net-(D5-K)") (class "Default")
      (node (ref "D5") (pin "2") (pinfunction "K_2") (pintype "passive"))
      (node (ref "R16") (pin "2") (pinfunction "2_2") (pintype "passive"))
    )
    (net (code "20") (name "Net-(D6-K)") (class "Default")
      (node (ref "C11") (pin "2") (pinfunction "2_2") (pintype "passive"))
      (node (ref "D6") (pin "2") (pinfunction "K_2") (pintype "passive"))
      (node (ref "R16") (pin "1") (pinfunction "1_1") (pintype "passive"))
      (node (ref "R17") (pin "2") (pinfunction "2_2") (pintype "passive"))
      (node (ref "SDC_test") (pin "1") (pinfunction "1_1") (pintype "passive"))
      (node (ref "U3") (pin "2") (pinfunction "1B_2") (pintype "input"))
    )
    (net (code "21") (name "Net-(DS1-A)") (class "Default")
      (node (ref "DS1") (pin "1") (pinfunction "A_1") (pintype "passive"))
      (node (ref "R7") (pin "2") (pinfunction "2_2") (pintype "passive"))
    )
    (net (code "22") (name "Net-(DS2-A)") (class "Default")
      (node (ref "DS2") (pin "1") (pinfunction "A_1") (pintype "passive"))
      (node (ref "R28") (pin "2") (pinfunction "2_2") (pintype "passive"))
    )
    (net (code "23") (name "Net-(IC1-B1)") (class "Default")
      (node (ref "IC1") (pin "13") (pinfunction "B1_13") (pintype "passive"))
      (node (ref "R22") (pin "2") (pinfunction "2_2") (pintype "passive"))
    )
    (net (code "24") (name "Net-(IC1-B2)") (class "Default")
      (node (ref "IC1") (pin "12") (pinfunction "B2_12") (pintype "passive"))
      (node (ref "R23") (pin "2") (pinfunction "2_2") (pintype "passive"))
    )
    (net (code "25") (name "Net-(IC1-B3)") (class "Default")
      (node (ref "IC1") (pin "11") (pinfunction "B3_11") (pintype "passive"))
      (node (ref "R26") (pin "1") (pinfunction "1_1") (pintype "passive"))
    )
    (net (code "26") (name "Net-(IC1-VREF_A)") (class "Default")
      (node (ref "IC1") (pin "1") (pinfunction "VREF_A_1") (pintype "passive"))
      (node (ref "R3") (pin "2") (pinfunction "2_2") (pintype "passive"))
    )
    (net (code "27") (name "Net-(IC1-VREF_B)") (class "Default")
      (node (ref "IC1") (pin "14") (pinfunction "VREF_B_14") (pintype "passive"))
      (node (ref "R4") (pin "2") (pinfunction "2_2") (pintype "passive"))
    )
    (net (code "28") (name "Net-(IC2-1A)") (class "Default")
      (node (ref "IC2") (pin "1") (pinfunction "1A_1") (pintype "passive"))
      (node (ref "RS1") (pin "11") (pinfunction "S2*_11") (pintype "passive"))
      (node (ref "U4") (pin "3") (pinfunction "~{RES}_3") (pintype "output"))
    )
    (net (code "29") (name "Net-(IC2-1Y)") (class "Default")
      (node (ref "IC2") (pin "6") (pinfunction "1Y_6") (pintype "passive"))
      (node (ref "RS1") (pin "4") (pinfunction "R0*_4") (pintype "passive"))
    )
    (net (code "30") (name "Net-(IC2-2A)") (class "Default")
      (node (ref "IC2") (pin "3") (pinfunction "2A_3") (pintype "passive"))
      (node (ref "R24") (pin "1") (pinfunction "1_1") (pintype "passive"))
      (node (ref "RS1") (pin "13") (pinfunction "Q0_13") (pintype "passive"))
    )
    (net (code "31") (name "Net-(IC2-2Y)") (class "Default")
      (node (ref "IC2") (pin "4") (pinfunction "2Y_4") (pintype "passive"))
      (node (ref "U5") (pin "1") (pinfunction "1A_1") (pintype "input"))
    )
    (net (code "32") (name "Net-(Q1-G)") (class "Default")
      (node (ref "Q1") (pin "1") (pinfunction "G_1") (pintype "passive"))
      (node (ref "R25") (pin "2") (pinfunction "2_2") (pintype "passive"))
    )
    (net (code "33") (name "Net-(RS1-E)") (class "Default")
      (node (ref "R2") (pin "1") (pinfunction "1_1") (pintype "passive"))
      (node (ref "RS1") (pin "5") (pinfunction "E_5") (pintype "passive"))
    )
    (net (code "34") (name "Net-(RS1-Q2)") (class "Default")
      (node (ref "RS1") (pin "10") (pinfunction "Q2_10") (pintype "passive"))
      (node (ref "U3") (pin "5") (pinfunction "2B_5") (pintype "input"))
      (node (ref "U3") (pin "9") (pinfunction "3A_9") (pintype "input"))
    )
    (net (code "35") (name "Net-(RS1-R2*)") (class "Default")
      (node (ref "R27") (pin "1") (pinfunction "1_1") (pintype "passive"))
      (node (ref "RS1") (pin "12") (pinfunction "R2*_12") (pintype "passive"))
    )
    (net (code "36") (name "Net-(RS1-S0*)") (class "Default")
      (node (ref "R20") (pin "2") (pinfunction "2_2") (pintype "passive"))
      (node (ref "RS1") (pin "3") (pinfunction "S0*_3") (pintype "passive"))
    )
    (net (code "37") (name "Net-(RS1-Vcc)") (class "Default")
      (node (ref "C3") (pin "2") (pinfunction "2_2") (pintype "passive"))
      (node (ref "R5") (pin "1") (pinfunction "1_1") (pintype "passive"))
      (node (ref "RS1") (pin "16") (pinfunction "Vcc_16") (pintype "passive"))
    )
    (net (code "38") (name "Net-(U1A-1A)") (class "Default")
      (node (ref "R22") (pin "1") (pinfunction "1_1") (pintype "passive"))
      (node (ref "U1") (pin "1") (pinfunction "1A_1") (pintype "input"))
    )
    (net (code "39") (name "Net-(U1A-1B)") (class "Default")
      (node (ref "R21") (pin "1") (pinfunction "1_1") (pintype "passive"))
      (node (ref "U1") (pin "2") (pinfunction "1B_2") (pintype "input"))
    )
    (net (code "40") (name "Net-(U1A-1Y)") (class "Default")
      (node (ref "R20") (pin "1") (pinfunction "1_1") (pintype "passive"))
      (node (ref "U1") (pin "3") (pinfunction "1Y_3") (pintype "output"))
    )
    (net (code "41") (name "Net-(U2-1Y)") (class "Default")
      (node (ref "R21") (pin "2") (pinfunction "2_2") (pintype "passive"))
      (node (ref "U2") (pin "4") (pinfunction "1Y_4") (pintype "output"))
    )
    (net (code "42") (name "Net-(U2-2A)") (class "Default")
      (node (ref "R18") (pin "1") (pinfunction "1_1") (pintype "passive"))
      (node (ref "U2") (pin "10") (pinfunction "3B_10") (pintype "input"))
      (node (ref "U2") (pin "11") (pinfunction "3A_11") (pintype "input"))
      (node (ref "U2") (pin "13") (pinfunction "4B_13") (pintype "input"))
      (node (ref "U2") (pin "14") (pinfunction "4A_14") (pintype "input"))
      (node (ref "U2") (pin "5") (pinfunction "2A_5") (pintype "input"))
      (node (ref "U2") (pin "6") (pinfunction "2B_6") (pintype "input"))
    )
    (net (code "43") (name "Net-(U2-~{A}{slash}B)") (class "Default")
      (node (ref "R23") (pin "1") (pinfunction "1_1") (pintype "passive"))
      (node (ref "U2") (pin "1") (pinfunction "~{A}/B_1") (pintype "input"))
    )
    (net (code "44") (name "Net-(U3A-1A)") (class "Default")
      (node (ref "U3") (pin "1") (pinfunction "1A_1") (pintype "input"))
      (node (ref "U4") (pin "5") (pinfunction "~{WDO}_5") (pintype "output"))
    )
    (net (code "45") (name "Net-(U3A-1Y)") (class "Default")
      (node (ref "U3") (pin "10") (pinfunction "3B_10") (pintype "input"))
      (node (ref "U3") (pin "3") (pinfunction "1Y_3") (pintype "output"))
      (node (ref "U5") (pin "2") (pinfunction "1B_2") (pintype "input"))
    )
    (net (code "46") (name "Net-(U3B-2A)") (class "Default")
      (node (ref "R24") (pin "2") (pinfunction "2_2") (pintype "passive"))
      (node (ref "U3") (pin "4") (pinfunction "2A_4") (pintype "input"))
    )
    (net (code "47") (name "Net-(U3B-2Y)") (class "Default")
      (node (ref "R25") (pin "1") (pinfunction "1_1") (pintype "passive"))
      (node (ref "U3") (pin "6") (pinfunction "2Y_6") (pintype "output"))
    )
    (net (code "48") (name "Net-(U3C-3Y)") (class "Default")
      (node (ref "R29") (pin "1") (pinfunction "1_1") (pintype "passive"))
      (node (ref "U3") (pin "8") (pinfunction "3Y_8") (pintype "output"))
    )
    (net (code "49") (name "Net-(U4-RP)") (class "Default")
      (node (ref "C5") (pin "1") (pinfunction "1_1") (pintype "passive"))
      (node (ref "U4") (pin "4") (pinfunction "RP_4") (pintype "input"))
    )
    (net (code "50") (name "Net-(U4-RTH)") (class "Default")
      (node (ref "R10") (pin "1") (pinfunction "1_1") (pintype "passive"))
      (node (ref "R13") (pin "2") (pinfunction "2_2") (pintype "passive"))
      (node (ref "U4") (pin "2") (pinfunction "RTH_2") (pintype "input"))
    )
    (net (code "51") (name "Net-(U4-WDI)") (class "Default")
      (node (ref "R26") (pin "2") (pinfunction "2_2") (pintype "passive"))
      (node (ref "U4") (pin "7") (pinfunction "WDI_7") (pintype "input"))
    )
    (net (code "52") (name "Net-(U4-WP)") (class "Default")
      (node (ref "C7") (pin "1") (pinfunction "1_1") (pintype "passive"))
      (node (ref "U4") (pin "6") (pinfunction "WP_6") (pintype "input"))
    )
    (net (code "53") (name "Net-(U5A-1Y)") (class "Default")
      (node (ref "R27") (pin "2") (pinfunction "2_2") (pintype "passive"))
      (node (ref "U5") (pin "3") (pinfunction "1Y_3") (pintype "output"))
    )
    (net (code "54") (name "unconnected-(IC1-A4-Pad5)") (class "Default")
      (node (ref "IC1") (pin "5") (pinfunction "A4_5") (pintype "passive"))
    )
    (net (code "55") (name "unconnected-(IC1-B4-Pad10)") (class "Default")
      (node (ref "IC1") (pin "10") (pinfunction "B4_10") (pintype "passive"))
    )
    (net (code "56") (name "unconnected-(IC1-NC_1-Pad6)") (class "Default")
      (node (ref "IC1") (pin "6") (pinfunction "NC_1_6") (pintype "passive+no_connect"))
    )
    (net (code "57") (name "unconnected-(IC1-NC_2-Pad9)") (class "Default")
      (node (ref "IC1") (pin "9") (pinfunction "NC_2_9") (pintype "passive+no_connect"))
    )
    (net (code "58") (name "unconnected-(J1-PadMH1)") (class "Default")
      (node (ref "J1") (pin "MH1") (pinfunction "MH1_MH1") (pintype "passive"))
    )
    (net (code "59") (name "unconnected-(J1-PadMH2)") (class "Default")
      (node (ref "J1") (pin "MH2") (pinfunction "MH2_MH2") (pintype "passive"))
    )
    (net (code "60") (name "unconnected-(K1-Pad4)") (class "Default")
      (node (ref "K1") (pin "4") (pinfunction "4_4") (pintype "passive"))
    )
    (net (code "61") (name "unconnected-(K1-Pad5)") (class "Default")
      (node (ref "K1") (pin "5") (pinfunction "5_5") (pintype "passive"))
    )
    (net (code "62") (name "unconnected-(K1-Pad6)") (class "Default")
      (node (ref "K1") (pin "6") (pinfunction "6_6") (pintype "passive"))
    )
    (net (code "63") (name "unconnected-(K1-Pad7)") (class "Default")
      (node (ref "K1") (pin "7") (pinfunction "7_7") (pintype "passive"))
    )
    (net (code "64") (name "unconnected-(K1-Pad8)") (class "Default")
      (node (ref "K1") (pin "8") (pinfunction "8_8") (pintype "passive"))
    )
    (net (code "65") (name "unconnected-(K1-Pad9)") (class "Default")
      (node (ref "K1") (pin "9") (pinfunction "9_9") (pintype "passive"))
    )
    (net (code "66") (name "unconnected-(K2-Pad2)") (class "Default")
      (node (ref "K2") (pin "2") (pinfunction "2_2") (pintype "passive"))
    )
    (net (code "67") (name "unconnected-(K2-Pad5)") (class "Default")
      (node (ref "K2") (pin "5") (pinfunction "5_5") (pintype "passive"))
    )
    (net (code "68") (name "unconnected-(K2-Pad6)") (class "Default")
      (node (ref "K2") (pin "6") (pinfunction "6_6") (pintype "passive"))
    )
    (net (code "69") (name "unconnected-(K2-Pad7)") (class "Default")
      (node (ref "K2") (pin "7") (pinfunction "7_7") (pintype "passive"))
    )
    (net (code "70") (name "unconnected-(K2-Pad8)") (class "Default")
      (node (ref "K2") (pin "8") (pinfunction "8_8") (pintype "passive"))
    )
    (net (code "71") (name "unconnected-(K2-Pad9)") (class "Default")
      (node (ref "K2") (pin "9") (pinfunction "9_9") (pintype "passive"))
    )
    (net (code "72") (name "unconnected-(RS1-NC-Pad2)") (class "Default")
      (node (ref "RS1") (pin "2") (pinfunction "NC_2") (pintype "passive"))
    )
    (net (code "73") (name "unconnected-(RS1-Q1-Pad9)") (class "Default")
      (node (ref "RS1") (pin "9") (pinfunction "Q1_9") (pintype "passive"))
    )
    (net (code "74") (name "unconnected-(RS1-Q3-Pad1)") (class "Default")
      (node (ref "RS1") (pin "1") (pinfunction "Q3_1") (pintype "passive"))
    )
    (net (code "75") (name "unconnected-(RS1-R1*-Pad6)") (class "Default")
      (node (ref "RS1") (pin "6") (pinfunction "R1*_6") (pintype "passive"))
    )
    (net (code "76") (name "unconnected-(RS1-R3*-Pad14)") (class "Default")
      (node (ref "RS1") (pin "14") (pinfunction "R3*_14") (pintype "passive"))
    )
    (net (code "77") (name "unconnected-(RS1-S1*-Pad7)") (class "Default")
      (node (ref "RS1") (pin "7") (pinfunction "S1*_7") (pintype "passive"))
    )
    (net (code "78") (name "unconnected-(RS1-S3*-Pad15)") (class "Default")
      (node (ref "RS1") (pin "15") (pinfunction "S3*_15") (pintype "passive"))
    )
    (net (code "79") (name "unconnected-(U2-2Y-Pad7)") (class "Default")
      (node (ref "U2") (pin "7") (pinfunction "2Y_7") (pintype "output"))
    )
    (net (code "80") (name "unconnected-(U2-3Y-Pad9)") (class "Default")
      (node (ref "U2") (pin "9") (pinfunction "3Y_9") (pintype "output"))
    )
    (net (code "81") (name "unconnected-(U2-4Y-Pad12)") (class "Default")
      (node (ref "U2") (pin "12") (pinfunction "4Y_12") (pintype "output"))
    )
  )
)
